# rpio_example.net
KiCad netlist of a schematic drawn in EAGLE
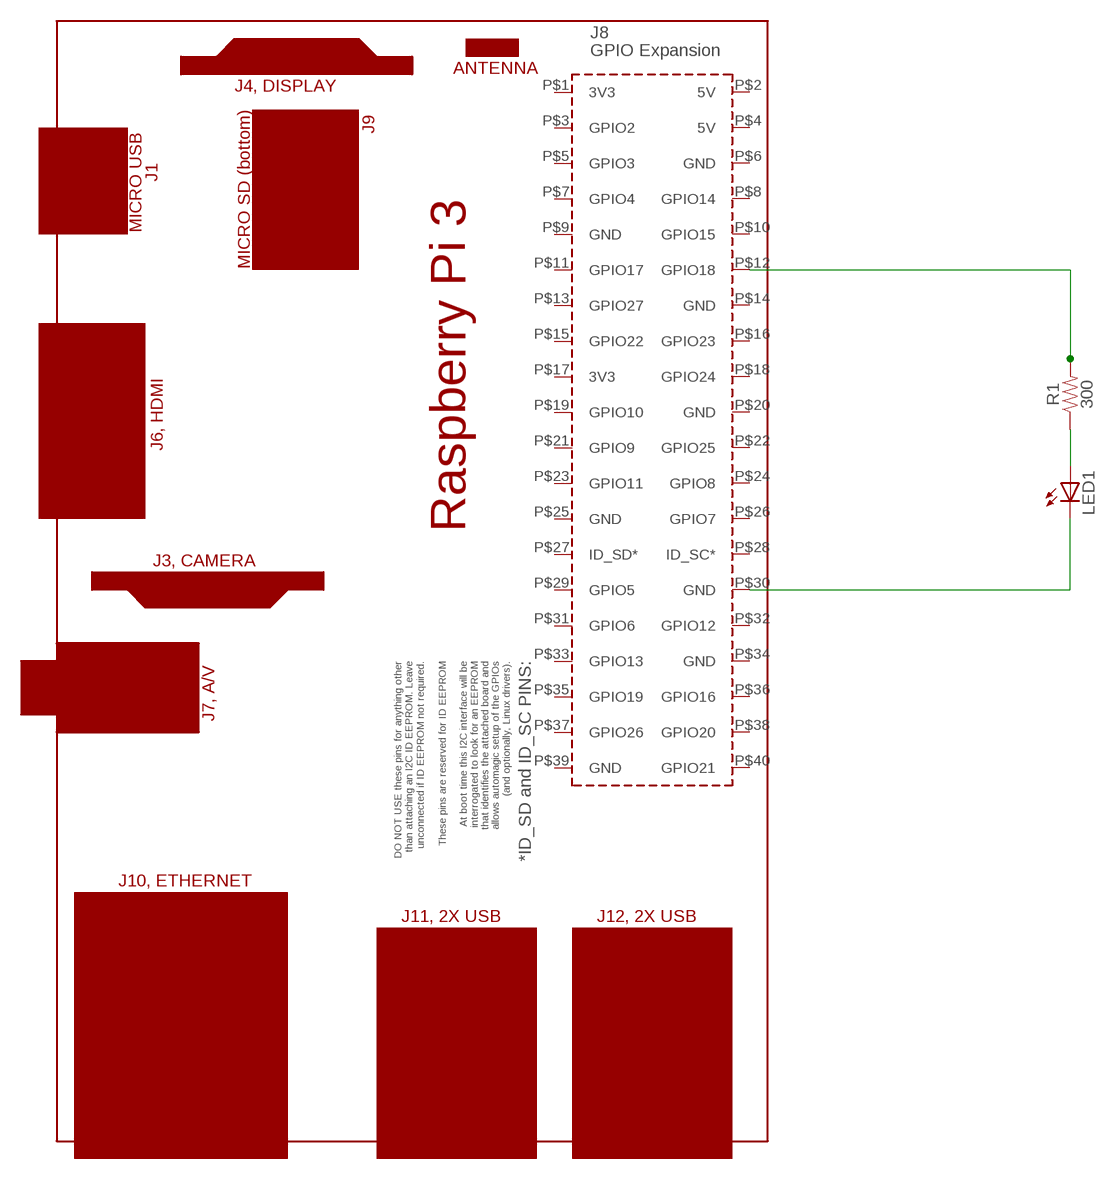
[diagram p0: schematic, sheet 1]

(export (version "E")
  (design (tool "Eeschema 10.0.6"))
  (components
    (comp (ref "LED1")
      (value "LED3MM")
      (footprint "eagle-import:LED3MM")
      (libsource (lib "eagle-import") (part "LED3MM"))
    )
    (comp (ref "PCB1")
      (value "RPI3RPI3")
      (footprint "eagle-import:RPI3")
      (libsource (lib "eagle-import") (part "RPI3RPI3"))
    )
    (comp (ref "R1")
      (value "300")
      (footprint "eagle-import:0603")
      (libsource (lib "eagle-import") (part "300OHM-0603-1/10W-1%"))
    )
  )
  (nets
    (net (code "1") (name "Net-(LED1-C)") (class "Default")
      (node (ref "LED1") (pin "K") (pinfunction "C_K") (pintype "passive"))
      (node (ref "PCB1") (pin "P$30") (pinfunction "GND_P$30") (pintype "bidirectional"))
    )
    (net (code "2") (name "Net-(LED1-PadA)") (class "Default")
      (node (ref "LED1") (pin "A") (pinfunction "A_A") (pintype "passive"))
      (node (ref "R1") (pin "1") (pinfunction "1_1") (pintype "passive"))
    )
    (net (code "3") (name "Net-(PCB1-GPIO18)") (class "Default")
      (node (ref "PCB1") (pin "P$12") (pinfunction "GPIO18_P$12") (pintype "bidirectional"))
      (node (ref "R1") (pin "2") (pinfunction "2_2") (pintype "passive"))
    )
    (net (code "4") (name "unconnected-(PCB1-3V3-PadP$1)") (class "Default")
      (node (ref "PCB1") (pin "P$1") (pinfunction "3V3_P$1") (pintype "bidirectional"))
    )
    (net (code "5") (name "unconnected-(PCB1-3V3-PadP$17)") (class "Default")
      (node (ref "PCB1") (pin "P$17") (pinfunction "3V3_P$17") (pintype "bidirectional"))
    )
    (net (code "6") (name "unconnected-(PCB1-5V-PadP$2)") (class "Default")
      (node (ref "PCB1") (pin "P$2") (pinfunction "5V_P$2") (pintype "bidirectional"))
    )
    (net (code "7") (name "unconnected-(PCB1-5V-PadP$4)") (class "Default")
      (node (ref "PCB1") (pin "P$4") (pinfunction "5V_P$4") (pintype "bidirectional"))
    )
    (net (code "8") (name "unconnected-(PCB1-GND-PadP$6)") (class "Default")
      (node (ref "PCB1") (pin "P$6") (pinfunction "GND_P$6") (pintype "bidirectional"))
    )
    (net (code "9") (name "unconnected-(PCB1-GND-PadP$9)") (class "Default")
      (node (ref "PCB1") (pin "P$9") (pinfunction "GND_P$9") (pintype "bidirectional"))
    )
    (net (code "10") (name "unconnected-(PCB1-GND-PadP$14)") (class "Default")
      (node (ref "PCB1") (pin "P$14") (pinfunction "GND_P$14") (pintype "bidirectional"))
    )
    (net (code "11") (name "unconnected-(PCB1-GND-PadP$20)") (class "Default")
      (node (ref "PCB1") (pin "P$20") (pinfunction "GND_P$20") (pintype "bidirectional"))
    )
    (net (code "12") (name "unconnected-(PCB1-GND-PadP$25)") (class "Default")
      (node (ref "PCB1") (pin "P$25") (pinfunction "GND_P$25") (pintype "bidirectional"))
    )
    (net (code "13") (name "unconnected-(PCB1-GND-PadP$34)") (class "Default")
      (node (ref "PCB1") (pin "P$34") (pinfunction "GND_P$34") (pintype "bidirectional"))
    )
    (net (code "14") (name "unconnected-(PCB1-GND-PadP$39)") (class "Default")
      (node (ref "PCB1") (pin "P$39") (pinfunction "GND_P$39") (pintype "bidirectional"))
    )
    (net (code "15") (name "unconnected-(PCB1-GPIO2-PadP$3)") (class "Default")
      (node (ref "PCB1") (pin "P$3") (pinfunction "GPIO2_P$3") (pintype "bidirectional"))
    )
    (net (code "16") (name "unconnected-(PCB1-GPIO3-PadP$5)") (class "Default")
      (node (ref "PCB1") (pin "P$5") (pinfunction "GPIO3_P$5") (pintype "bidirectional"))
    )
    (net (code "17") (name "unconnected-(PCB1-GPIO4-PadP$7)") (class "Default")
      (node (ref "PCB1") (pin "P$7") (pinfunction "GPIO4_P$7") (pintype "bidirectional"))
    )
    (net (code "18") (name "unconnected-(PCB1-GPIO5-PadP$29)") (class "Default")
      (node (ref "PCB1") (pin "P$29") (pinfunction "GPIO5_P$29") (pintype "bidirectional"))
    )
    (net (code "19") (name "unconnected-(PCB1-GPIO6-PadP$31)") (class "Default")
      (node (ref "PCB1") (pin "P$31") (pinfunction "GPIO6_P$31") (pintype "bidirectional"))
    )
    (net (code "20") (name "unconnected-(PCB1-GPIO7-PadP$26)") (class "Default")
      (node (ref "PCB1") (pin "P$26") (pinfunction "GPIO7_P$26") (pintype "bidirectional"))
    )
    (net (code "21") (name "unconnected-(PCB1-GPIO8-PadP$24)") (class "Default")
      (node (ref "PCB1") (pin "P$24") (pinfunction "GPIO8_P$24") (pintype "bidirectional"))
    )
    (net (code "22") (name "unconnected-(PCB1-GPIO9-PadP$21)") (class "Default")
      (node (ref "PCB1") (pin "P$21") (pinfunction "GPIO9_P$21") (pintype "bidirectional"))
    )
    (net (code "23") (name "unconnected-(PCB1-GPIO10-PadP$19)") (class "Default")
      (node (ref "PCB1") (pin "P$19") (pinfunction "GPIO10_P$19") (pintype "bidirectional"))
    )
    (net (code "24") (name "unconnected-(PCB1-GPIO11-PadP$23)") (class "Default")
      (node (ref "PCB1") (pin "P$23") (pinfunction "GPIO11_P$23") (pintype "bidirectional"))
    )
    (net (code "25") (name "unconnected-(PCB1-GPIO12-PadP$32)") (class "Default")
      (node (ref "PCB1") (pin "P$32") (pinfunction "GPIO12_P$32") (pintype "bidirectional"))
    )
    (net (code "26") (name "unconnected-(PCB1-GPIO13-PadP$33)") (class "Default")
      (node (ref "PCB1") (pin "P$33") (pinfunction "GPIO13_P$33") (pintype "bidirectional"))
    )
    (net (code "27") (name "unconnected-(PCB1-GPIO14-PadP$8)") (class "Default")
      (node (ref "PCB1") (pin "P$8") (pinfunction "GPIO14_P$8") (pintype "bidirectional"))
    )
    (net (code "28") (name "unconnected-(PCB1-GPIO15-PadP$10)") (class "Default")
      (node (ref "PCB1") (pin "P$10") (pinfunction "GPIO15_P$10") (pintype "bidirectional"))
    )
    (net (code "29") (name "unconnected-(PCB1-GPIO16-PadP$36)") (class "Default")
      (node (ref "PCB1") (pin "P$36") (pinfunction "GPIO16_P$36") (pintype "bidirectional"))
    )
    (net (code "30") (name "unconnected-(PCB1-GPIO17-PadP$11)") (class "Default")
      (node (ref "PCB1") (pin "P$11") (pinfunction "GPIO17_P$11") (pintype "bidirectional"))
    )
    (net (code "31") (name "unconnected-(PCB1-GPIO19-PadP$35)") (class "Default")
      (node (ref "PCB1") (pin "P$35") (pinfunction "GPIO19_P$35") (pintype "bidirectional"))
    )
    (net (code "32") (name "unconnected-(PCB1-GPIO20-PadP$38)") (class "Default")
      (node (ref "PCB1") (pin "P$38") (pinfunction "GPIO20_P$38") (pintype "bidirectional"))
    )
    (net (code "33") (name "unconnected-(PCB1-GPIO21-PadP$40)") (class "Default")
      (node (ref "PCB1") (pin "P$40") (pinfunction "GPIO21_P$40") (pintype "bidirectional"))
    )
    (net (code "34") (name "unconnected-(PCB1-GPIO22-PadP$15)") (class "Default")
      (node (ref "PCB1") (pin "P$15") (pinfunction "GPIO22_P$15") (pintype "bidirectional"))
    )
    (net (code "35") (name "unconnected-(PCB1-GPIO23-PadP$16)") (class "Default")
      (node (ref "PCB1") (pin "P$16") (pinfunction "GPIO23_P$16") (pintype "bidirectional"))
    )
    (net (code "36") (name "unconnected-(PCB1-GPIO24-PadP$18)") (class "Default")
      (node (ref "PCB1") (pin "P$18") (pinfunction "GPIO24_P$18") (pintype "bidirectional"))
    )
    (net (code "37") (name "unconnected-(PCB1-GPIO25-PadP$22)") (class "Default")
      (node (ref "PCB1") (pin "P$22") (pinfunction "GPIO25_P$22") (pintype "bidirectional"))
    )
    (net (code "38") (name "unconnected-(PCB1-GPIO26-PadP$37)") (class "Default")
      (node (ref "PCB1") (pin "P$37") (pinfunction "GPIO26_P$37") (pintype "bidirectional"))
    )
    (net (code "39") (name "unconnected-(PCB1-GPIO27-PadP$13)") (class "Default")
      (node (ref "PCB1") (pin "P$13") (pinfunction "GPIO27_P$13") (pintype "bidirectional"))
    )
    (net (code "40") (name "unconnected-(PCB1-ID_SC*-PadP$28)") (class "Default")
      (node (ref "PCB1") (pin "P$28") (pinfunction "ID_SC*_P$28") (pintype "bidirectional"))
    )
    (net (code "41") (name "unconnected-(PCB1-ID_SD*-PadP$27)") (class "Default")
      (node (ref "PCB1") (pin "P$27") (pinfunction "ID_SD*_P$27") (pintype "bidirectional"))
    )
  )
)
